# design.net
KiCad netlist of a schematic drawn in Altium Designer
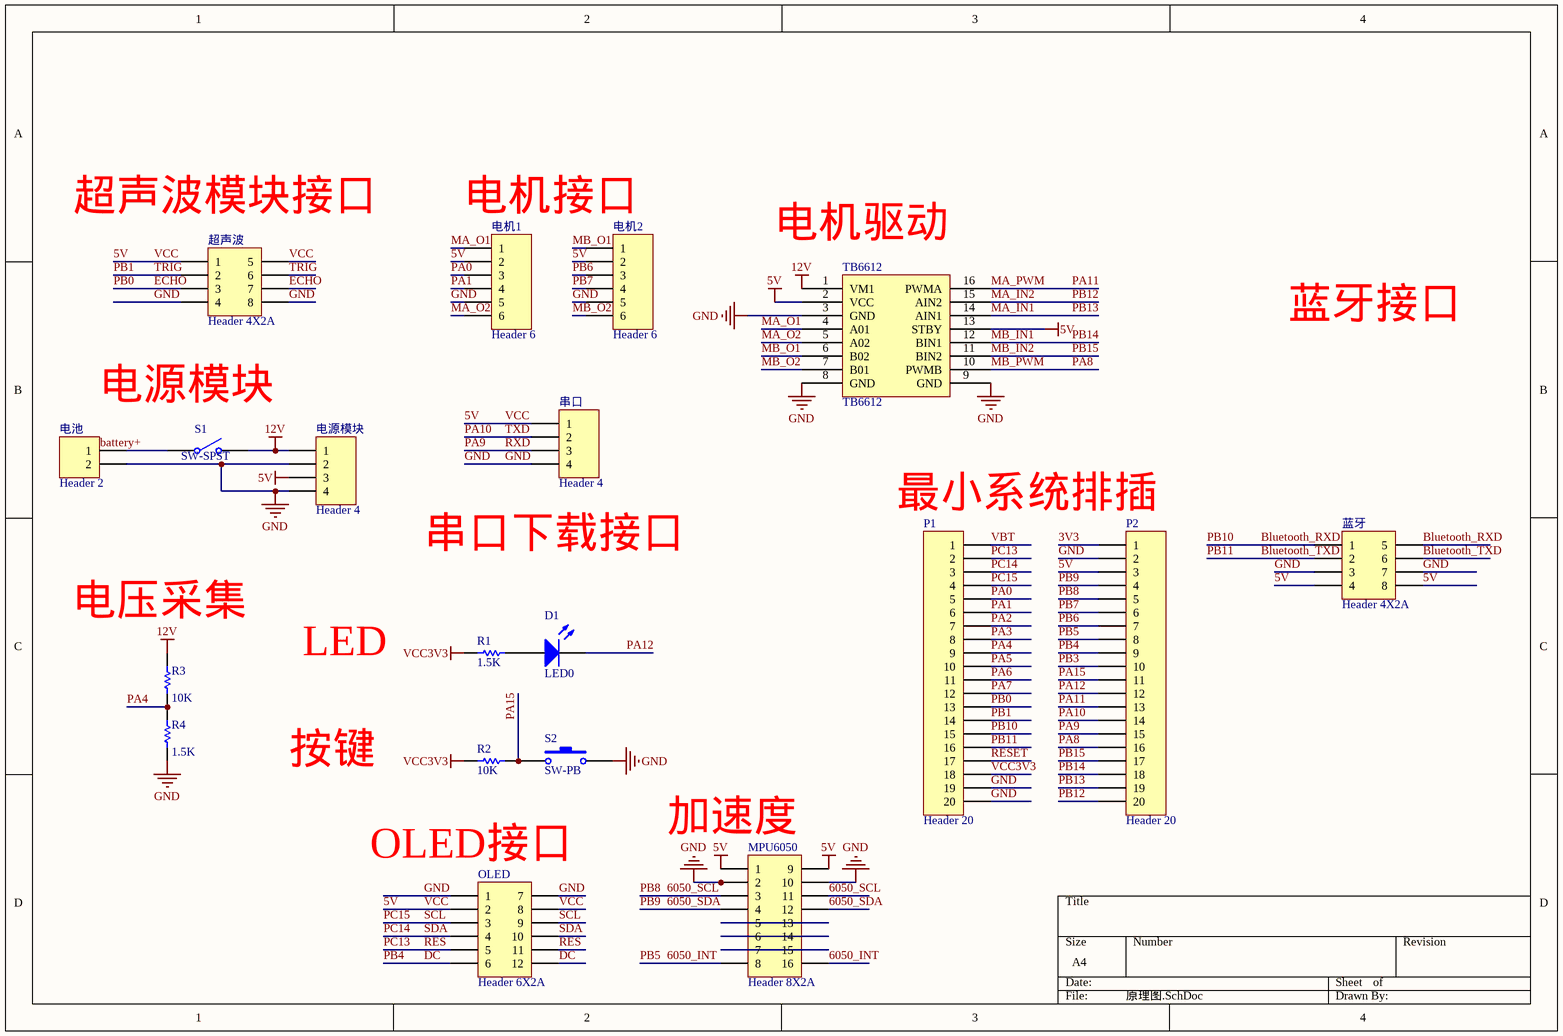
[diagram p0: 原理图.SchDoc]

(export (version "E")
  (design (tool "Eeschema 10.0.6"))
  (components
    (comp (ref "D1")
      (value "LED0")
      (footprint "LED")
      (description "Typical INFRARED GaAs LED")
      (fields (field (name "PUBLISHER") "Altium Limited"))
      (libsource (lib "Miscellaneous Devices") (part "LED0"))
    )
    (comp (ref "MPU6050")
      (value "Header 8X2A")
      (footprint "HDR2X8_6050")
      (description "Header, 8-Pin, Dual row")
      (fields (field (name "PUBLISHER") "Altium Limited"))
      (libsource (lib "Miscellaneous Connectors") (part "Header 8X2A"))
    )
    (comp (ref "OLED")
      (value "Header 6X2A")
      (footprint "OLED-6PIN")
      (description "Header, 6-Pin, Dual row")
      (fields (field (name "PUBLISHER") "Altium Limited"))
      (libsource (lib "Miscellaneous Connectors") (part "Header 6X2A"))
    )
    (comp (ref "P1")
      (value "Header 20")
      (footprint "HDR1X20")
      (description "Header, 20-Pin")
      (fields (field (name "PUBLISHER") "Altium Limited"))
      (libsource (lib "") (part "Header 20_1"))
    )
    (comp (ref "P2")
      (value "Header 20")
      (footprint "HDR1X20")
      (description "Header, 20-Pin")
      (fields (field (name "PUBLISHER") "Altium Limited"))
      (libsource (lib "Miscellaneous Connectors") (part "Header 20"))
    )
    (comp (ref "R1")
      (value "1.5K")
      (footprint "RES")
      (description "Semiconductor Resistor")
      (fields (field (name "Comment") "Res Semi") (field (name "PUBLISHER") "Altium Limited"))
      (libsource (lib "Miscellaneous Devices") (part "Res Semi"))
    )
    (comp (ref "R2")
      (value "10K")
      (footprint "RES")
      (description "Semiconductor Resistor")
      (fields (field (name "Comment") "Res Semi") (field (name "PUBLISHER") "Altium Limited"))
      (libsource (lib "Miscellaneous Devices") (part "Res Semi"))
    )
    (comp (ref "R3")
      (value "10K")
      (footprint "RES")
      (description "Semiconductor Resistor")
      (fields (field (name "Comment") "Res Semi") (field (name "PUBLISHER") "Altium Limited"))
      (libsource (lib "Miscellaneous Devices") (part "Res Semi"))
    )
    (comp (ref "R4")
      (value "1.5K")
      (footprint "RES")
      (description "Semiconductor Resistor")
      (fields (field (name "Comment") "Res Semi") (field (name "PUBLISHER") "Altium Limited"))
      (libsource (lib "Miscellaneous Devices") (part "Res Semi"))
    )
    (comp (ref "S1")
      (value "SW-SPST")
      (footprint "SW-4X3")
      (description "Single-Pole, Single-Throw Switch")
      (fields (field (name "PUBLISHER") "Altium Limited"))
      (libsource (lib "Miscellaneous Devices") (part "SW-SPST"))
    )
    (comp (ref "S2")
      (value "SW-PB")
      (footprint "SW12*12")
      (description "Switch")
      (fields (field (name "PUBLISHER") "Altium Limited"))
      (libsource (lib "Miscellaneous Devices") (part "SW-PB"))
    )
    (comp (ref "TB6612") (value "TB6612") (footprint "TB6612") (libsource (lib "Schlib1") (part "TB6612")))
    (comp (ref "串口")
      (value "Header 4")
      (footprint "HDR1X4")
      (description "Header, 4-Pin")
      (fields (field (name "PUBLISHER") "Altium Limited"))
      (libsource (lib "Miscellaneous Connectors") (part "Header 4"))
    )
    (comp (ref "电机1")
      (value "Header 6")
      (footprint "HDR1X6 - XH弯")
      (description "不用焊")
      (fields (field (name "PUBLISHER") "Altium Limited"))
      (libsource (lib "Miscellaneous Connectors") (part "Header 6"))
    )
    (comp (ref "电机2")
      (value "Header 6")
      (footprint "HDR1X6 - XH弯")
      (description "不用焊")
      (fields (field (name "PUBLISHER") "Altium Limited"))
      (libsource (lib "Miscellaneous Connectors") (part "Header 6"))
    )
    (comp (ref "电池")
      (value "Header 2")
      (footprint "2P*5.08")
      (description "Header, 2-Pin")
      (fields (field (name "PUBLISHER") "Altium Limited"))
      (libsource (lib "Miscellaneous Connectors") (part "Header 2"))
    )
    (comp (ref "电源模块")
      (value "Header 4")
      (footprint "LM2596-new")
      (description "Header, 4-Pin")
      (fields (field (name "PUBLISHER") "Altium Limited"))
      (libsource (lib "Miscellaneous Connectors") (part "Header 4"))
    )
    (comp (ref "蓝牙")
      (value "Header 4X2A")
      (footprint "BLUETOOTH")
      (description "Header, 4-Pin, Dual row")
      (fields (field (name "PUBLISHER") "Altium Limited"))
      (libsource (lib "Miscellaneous Connectors") (part "Header 4X2A"))
    )
    (comp (ref "超声波")
      (value "Header 4X2A")
      (footprint "HDR2X4_CEN")
      (description "Header, 4-Pin, Dual row")
      (fields (field (name "PUBLISHER") "Altium Limited"))
      (libsource (lib "Miscellaneous Connectors") (part "Header 4X2A"))
    )
  )
  (nets
    (net (code "1") (name "/3V3") (class "Default")
      (node (ref "P2") (pin "1") (pinfunction "1_1") (pintype "passive"))
    )
    (net (code "2") (name "/6050_INT") (class "Default")
      (node (ref "MPU6050") (pin "16") (pinfunction "16_16") (pintype "passive"))
      (node (ref "MPU6050") (pin "8") (pinfunction "8_8") (pintype "passive"))
      (node (ref "P2") (pin "8") (pinfunction "8_8") (pintype "passive"))
    )
    (net (code "3") (name "/6050_SCL") (class "Default")
      (node (ref "MPU6050") (pin "11") (pinfunction "11_11") (pintype "passive"))
      (node (ref "MPU6050") (pin "3") (pinfunction "3_3") (pintype "passive"))
      (node (ref "P2") (pin "5") (pinfunction "5_5") (pintype "passive"))
    )
    (net (code "4") (name "/6050_SDA") (class "Default")
      (node (ref "MPU6050") (pin "12") (pinfunction "12_12") (pintype "passive"))
      (node (ref "MPU6050") (pin "4") (pinfunction "4_4") (pintype "passive"))
      (node (ref "P2") (pin "4") (pinfunction "4_4") (pintype "passive"))
    )
    (net (code "5") (name "/Bluetooth_RXD") (class "Default")
      (node (ref "P1") (pin "15") (pinfunction "15_15") (pintype "passive"))
      (node (ref "蓝牙") (pin "1") (pinfunction "1_1") (pintype "passive"))
      (node (ref "蓝牙") (pin "5") (pinfunction "5_5") (pintype "passive"))
    )
    (net (code "6") (name "/Bluetooth_TXD") (class "Default")
      (node (ref "P1") (pin "16") (pinfunction "16_16") (pintype "passive"))
      (node (ref "蓝牙") (pin "2") (pinfunction "2_2") (pintype "passive"))
      (node (ref "蓝牙") (pin "6") (pinfunction "6_6") (pintype "passive"))
    )
    (net (code "7") (name "/DC") (class "Default")
      (node (ref "OLED") (pin "12") (pinfunction "12_12") (pintype "passive"))
      (node (ref "OLED") (pin "6") (pinfunction "6_6") (pintype "passive"))
      (node (ref "P2") (pin "9") (pinfunction "9_9") (pintype "passive"))
    )
    (net (code "8") (name "/ECHO") (class "Default")
      (node (ref "P1") (pin "13") (pinfunction "13_13") (pintype "passive"))
      (node (ref "超声波") (pin "3") (pinfunction "3_3") (pintype "passive"))
      (node (ref "超声波") (pin "7") (pinfunction "7_7") (pintype "passive"))
    )
    (net (code "9") (name "/MA_IN1") (class "Default")
      (node (ref "P2") (pin "19") (pinfunction "19_19") (pintype "passive"))
      (node (ref "TB6612") (pin "14") (pinfunction "AIN1_14") (pintype "passive"))
    )
    (net (code "10") (name "/MA_IN2") (class "Default")
      (node (ref "P2") (pin "20") (pinfunction "20_20") (pintype "passive"))
      (node (ref "TB6612") (pin "15") (pinfunction "AIN2_15") (pintype "passive"))
    )
    (net (code "11") (name "/MA_O1") (class "Default")
      (node (ref "TB6612") (pin "4") (pinfunction "A01_4") (pintype "passive"))
      (node (ref "电机1") (pin "1") (pinfunction "1_1") (pintype "passive"))
    )
    (net (code "12") (name "/MA_O2") (class "Default")
      (node (ref "TB6612") (pin "5") (pinfunction "A02_5") (pintype "passive"))
      (node (ref "电机1") (pin "6") (pinfunction "6_6") (pintype "passive"))
    )
    (net (code "13") (name "/MA_PWM") (class "Default")
      (node (ref "P2") (pin "13") (pinfunction "13_13") (pintype "passive"))
      (node (ref "TB6612") (pin "16") (pinfunction "PWMA_16") (pintype "passive"))
    )
    (net (code "14") (name "/MB_IN1") (class "Default")
      (node (ref "P2") (pin "18") (pinfunction "18_18") (pintype "passive"))
      (node (ref "TB6612") (pin "12") (pinfunction "BIN1_12") (pintype "passive"))
    )
    (net (code "15") (name "/MB_IN2") (class "Default")
      (node (ref "P2") (pin "17") (pinfunction "17_17") (pintype "passive"))
      (node (ref "TB6612") (pin "11") (pinfunction "BIN2_11") (pintype "passive"))
    )
    (net (code "16") (name "/MB_O1") (class "Default")
      (node (ref "TB6612") (pin "6") (pinfunction "B02_6") (pintype "passive"))
      (node (ref "电机2") (pin "1") (pinfunction "1_1") (pintype "passive"))
    )
    (net (code "17") (name "/MB_O2") (class "Default")
      (node (ref "TB6612") (pin "7") (pinfunction "B01_7") (pintype "passive"))
      (node (ref "电机2") (pin "6") (pinfunction "6_6") (pintype "passive"))
    )
    (net (code "18") (name "/MB_PWM") (class "Default")
      (node (ref "P2") (pin "16") (pinfunction "16_16") (pintype "passive"))
      (node (ref "TB6612") (pin "10") (pinfunction "PWMB_10") (pintype "passive"))
    )
    (net (code "19") (name "/PA0") (class "Default")
      (node (ref "P1") (pin "5") (pinfunction "5_5") (pintype "passive"))
      (node (ref "电机1") (pin "3") (pinfunction "3_3") (pintype "passive"))
    )
    (net (code "20") (name "/PA1") (class "Default")
      (node (ref "P1") (pin "6") (pinfunction "6_6") (pintype "passive"))
      (node (ref "电机1") (pin "4") (pinfunction "4_4") (pintype "passive"))
    )
    (net (code "21") (name "/PA2") (class "Default")
      (node (ref "P1") (pin "7") (pinfunction "7_7") (pintype "passive"))
    )
    (net (code "22") (name "/PA3") (class "Default")
      (node (ref "P1") (pin "8") (pinfunction "8_8") (pintype "passive"))
    )
    (net (code "23") (name "/PA4") (class "Default")
      (node (ref "P1") (pin "9") (pinfunction "9_9") (pintype "passive"))
      (node (ref "R3") (pin "1") (pinfunction "1_1") (pintype "passive"))
      (node (ref "R4") (pin "2") (pinfunction "2_2") (pintype "passive"))
    )
    (net (code "24") (name "/PA5") (class "Default")
      (node (ref "P1") (pin "10") (pinfunction "10_10") (pintype "passive"))
    )
    (net (code "25") (name "/PA6") (class "Default")
      (node (ref "P1") (pin "11") (pinfunction "11_11") (pintype "passive"))
    )
    (net (code "26") (name "/PA7") (class "Default")
      (node (ref "P1") (pin "12") (pinfunction "12_12") (pintype "passive"))
    )
    (net (code "27") (name "/PA9") (class "Default")
      (node (ref "P2") (pin "15") (pinfunction "15_15") (pintype "passive"))
      (node (ref "串口") (pin "3") (pinfunction "3_3") (pintype "passive"))
    )
    (net (code "28") (name "/PA10") (class "Default")
      (node (ref "P2") (pin "14") (pinfunction "14_14") (pintype "passive"))
      (node (ref "串口") (pin "2") (pinfunction "2_2") (pintype "passive"))
    )
    (net (code "29") (name "/PA12") (class "Default")
      (node (ref "D1") (pin "2") (pinfunction "K_2") (pintype "passive"))
      (node (ref "P2") (pin "12") (pinfunction "12_12") (pintype "passive"))
    )
    (net (code "30") (name "/PA15") (class "Default")
      (node (ref "P2") (pin "11") (pinfunction "11_11") (pintype "passive"))
      (node (ref "R2") (pin "1") (pinfunction "1_1") (pintype "passive"))
      (node (ref "S2") (pin "1") (pinfunction "1_1") (pintype "passive"))
    )
    (net (code "31") (name "/PB1") (class "Default")
      (node (ref "P1") (pin "14") (pinfunction "14_14") (pintype "passive"))
      (node (ref "超声波") (pin "2") (pinfunction "2_2") (pintype "passive"))
      (node (ref "超声波") (pin "6") (pinfunction "6_6") (pintype "passive"))
    )
    (net (code "32") (name "/PB3") (class "Default")
      (node (ref "P2") (pin "10") (pinfunction "10_10") (pintype "passive"))
    )
    (net (code "33") (name "/PB6") (class "Default")
      (node (ref "P2") (pin "7") (pinfunction "7_7") (pintype "passive"))
      (node (ref "电机2") (pin "3") (pinfunction "3_3") (pintype "passive"))
    )
    (net (code "34") (name "/PB7") (class "Default")
      (node (ref "P2") (pin "6") (pinfunction "6_6") (pintype "passive"))
      (node (ref "电机2") (pin "4") (pinfunction "4_4") (pintype "passive"))
    )
    (net (code "35") (name "/PC13") (class "Default")
      (node (ref "OLED") (pin "11") (pinfunction "11_11") (pintype "passive"))
      (node (ref "OLED") (pin "5") (pinfunction "5_5") (pintype "passive"))
      (node (ref "P1") (pin "2") (pinfunction "2_2") (pintype "passive"))
    )
    (net (code "36") (name "/PC14") (class "Default")
      (node (ref "OLED") (pin "10") (pinfunction "10_10") (pintype "passive"))
      (node (ref "OLED") (pin "4") (pinfunction "4_4") (pintype "passive"))
      (node (ref "P1") (pin "3") (pinfunction "3_3") (pintype "passive"))
    )
    (net (code "37") (name "/PC15") (class "Default")
      (node (ref "OLED") (pin "3") (pinfunction "3_3") (pintype "passive"))
      (node (ref "OLED") (pin "9") (pinfunction "9_9") (pintype "passive"))
      (node (ref "P1") (pin "4") (pinfunction "4_4") (pintype "passive"))
    )
    (net (code "38") (name "/RESET") (class "Default")
      (node (ref "P1") (pin "17") (pinfunction "17_17") (pintype "passive"))
    )
    (net (code "39") (name "/VBT") (class "Default")
      (node (ref "P1") (pin "1") (pinfunction "1_1") (pintype "passive"))
    )
    (net (code "41") (name "5V") (class "Default")
      (node (ref "MPU6050") (pin "1") (pinfunction "1_1") (pintype "passive"))
      (node (ref "MPU6050") (pin "9") (pinfunction "9_9") (pintype "passive"))
      (node (ref "OLED") (pin "2") (pinfunction "2_2") (pintype "passive"))
      (node (ref "OLED") (pin "8") (pinfunction "8_8") (pintype "passive"))
      (node (ref "P2") (pin "3") (pinfunction "3_3") (pintype "passive"))
      (node (ref "TB6612") (pin "13") (pinfunction "STBY_13") (pintype "passive"))
      (node (ref "TB6612") (pin "2") (pinfunction "VCC_2") (pintype "passive"))
      (node (ref "串口") (pin "1") (pinfunction "1_1") (pintype "passive"))
      (node (ref "电机1") (pin "2") (pinfunction "2_2") (pintype "passive"))
      (node (ref "电机2") (pin "2") (pinfunction "2_2") (pintype "passive"))
      (node (ref "电源模块") (pin "3") (pinfunction "3_3") (pintype "passive"))
      (node (ref "蓝牙") (pin "4") (pinfunction "4_4") (pintype "passive"))
      (node (ref "蓝牙") (pin "8") (pinfunction "8_8") (pintype "passive"))
      (node (ref "超声波") (pin "1") (pinfunction "1_1") (pintype "passive"))
      (node (ref "超声波") (pin "5") (pinfunction "5_5") (pintype "passive"))
    )
    (net (code "42") (name "12V") (class "Default")
      (node (ref "R3") (pin "2") (pinfunction "2_2") (pintype "passive"))
      (node (ref "S1") (pin "2") (pinfunction "NO_2") (pintype "passive"))
      (node (ref "TB6612") (pin "1") (pinfunction "VM1_1") (pintype "passive"))
      (node (ref "电源模块") (pin "1") (pinfunction "1_1") (pintype "passive"))
    )
    (net (code "43") (name "GND") (class "Default")
      (node (ref "MPU6050") (pin "10") (pinfunction "10_10") (pintype "passive"))
      (node (ref "MPU6050") (pin "2") (pinfunction "2_2") (pintype "passive"))
      (node (ref "OLED") (pin "1") (pinfunction "1_1") (pintype "passive"))
      (node (ref "OLED") (pin "7") (pinfunction "7_7") (pintype "passive"))
      (node (ref "P1") (pin "19") (pinfunction "19_19") (pintype "passive"))
      (node (ref "P1") (pin "20") (pinfunction "20_20") (pintype "passive"))
      (node (ref "P2") (pin "2") (pinfunction "2_2") (pintype "passive"))
      (node (ref "R4") (pin "1") (pinfunction "1_1") (pintype "passive"))
      (node (ref "S2") (pin "2") (pinfunction "2_2") (pintype "passive"))
      (node (ref "TB6612") (pin "3") (pinfunction "GND_3") (pintype "passive"))
      (node (ref "TB6612") (pin "8") (pinfunction "GND_8") (pintype "passive"))
      (node (ref "TB6612") (pin "9") (pinfunction "GND_9") (pintype "passive"))
      (node (ref "串口") (pin "4") (pinfunction "4_4") (pintype "passive"))
      (node (ref "电机1") (pin "5") (pinfunction "5_5") (pintype "passive"))
      (node (ref "电机2") (pin "5") (pinfunction "5_5") (pintype "passive"))
      (node (ref "电池") (pin "2") (pinfunction "2_2") (pintype "passive"))
      (node (ref "电源模块") (pin "2") (pinfunction "2_2") (pintype "passive"))
      (node (ref "电源模块") (pin "4") (pinfunction "4_4") (pintype "passive"))
      (node (ref "蓝牙") (pin "3") (pinfunction "3_3") (pintype "passive"))
      (node (ref "蓝牙") (pin "7") (pinfunction "7_7") (pintype "passive"))
      (node (ref "超声波") (pin "4") (pinfunction "4_4") (pintype "passive"))
      (node (ref "超声波") (pin "8") (pinfunction "8_8") (pintype "passive"))
    )
    (net (code "44") (name "Net-(D1-A)") (class "Default")
      (node (ref "D1") (pin "1") (pinfunction "A_1") (pintype "passive"))
      (node (ref "R1") (pin "1") (pinfunction "1_1") (pintype "passive"))
    )
    (net (code "45") (name "Net-(MPU6050-Pad13)") (class "Default")
      (node (ref "MPU6050") (pin "13") (pinfunction "13_13") (pintype "passive"))
      (node (ref "MPU6050") (pin "5") (pinfunction "5_5") (pintype "passive"))
    )
    (net (code "46") (name "Net-(MPU6050-Pad14)") (class "Default")
      (node (ref "MPU6050") (pin "14") (pinfunction "14_14") (pintype "passive"))
      (node (ref "MPU6050") (pin "6") (pinfunction "6_6") (pintype "passive"))
    )
    (net (code "47") (name "Net-(MPU6050-Pad15)") (class "Default")
      (node (ref "MPU6050") (pin "15") (pinfunction "15_15") (pintype "passive"))
      (node (ref "MPU6050") (pin "7") (pinfunction "7_7") (pintype "passive"))
    )
    (net (code "48") (name "Net-(S1-COMMON)") (class "Default")
      (node (ref "S1") (pin "1") (pinfunction "COMMON_1") (pintype "passive"))
      (node (ref "电池") (pin "1") (pinfunction "1_1") (pintype "passive"))
    )
    (net (code "49") (name "VCC3V3") (class "Default")
      (node (ref "P1") (pin "18") (pinfunction "18_18") (pintype "passive"))
      (node (ref "R1") (pin "2") (pinfunction "2_2") (pintype "passive"))
      (node (ref "R2") (pin "2") (pinfunction "2_2") (pintype "passive"))
    )
  )
)
